# Ethernet.net
KiCad netlist of a schematic drawn in Altium Designer
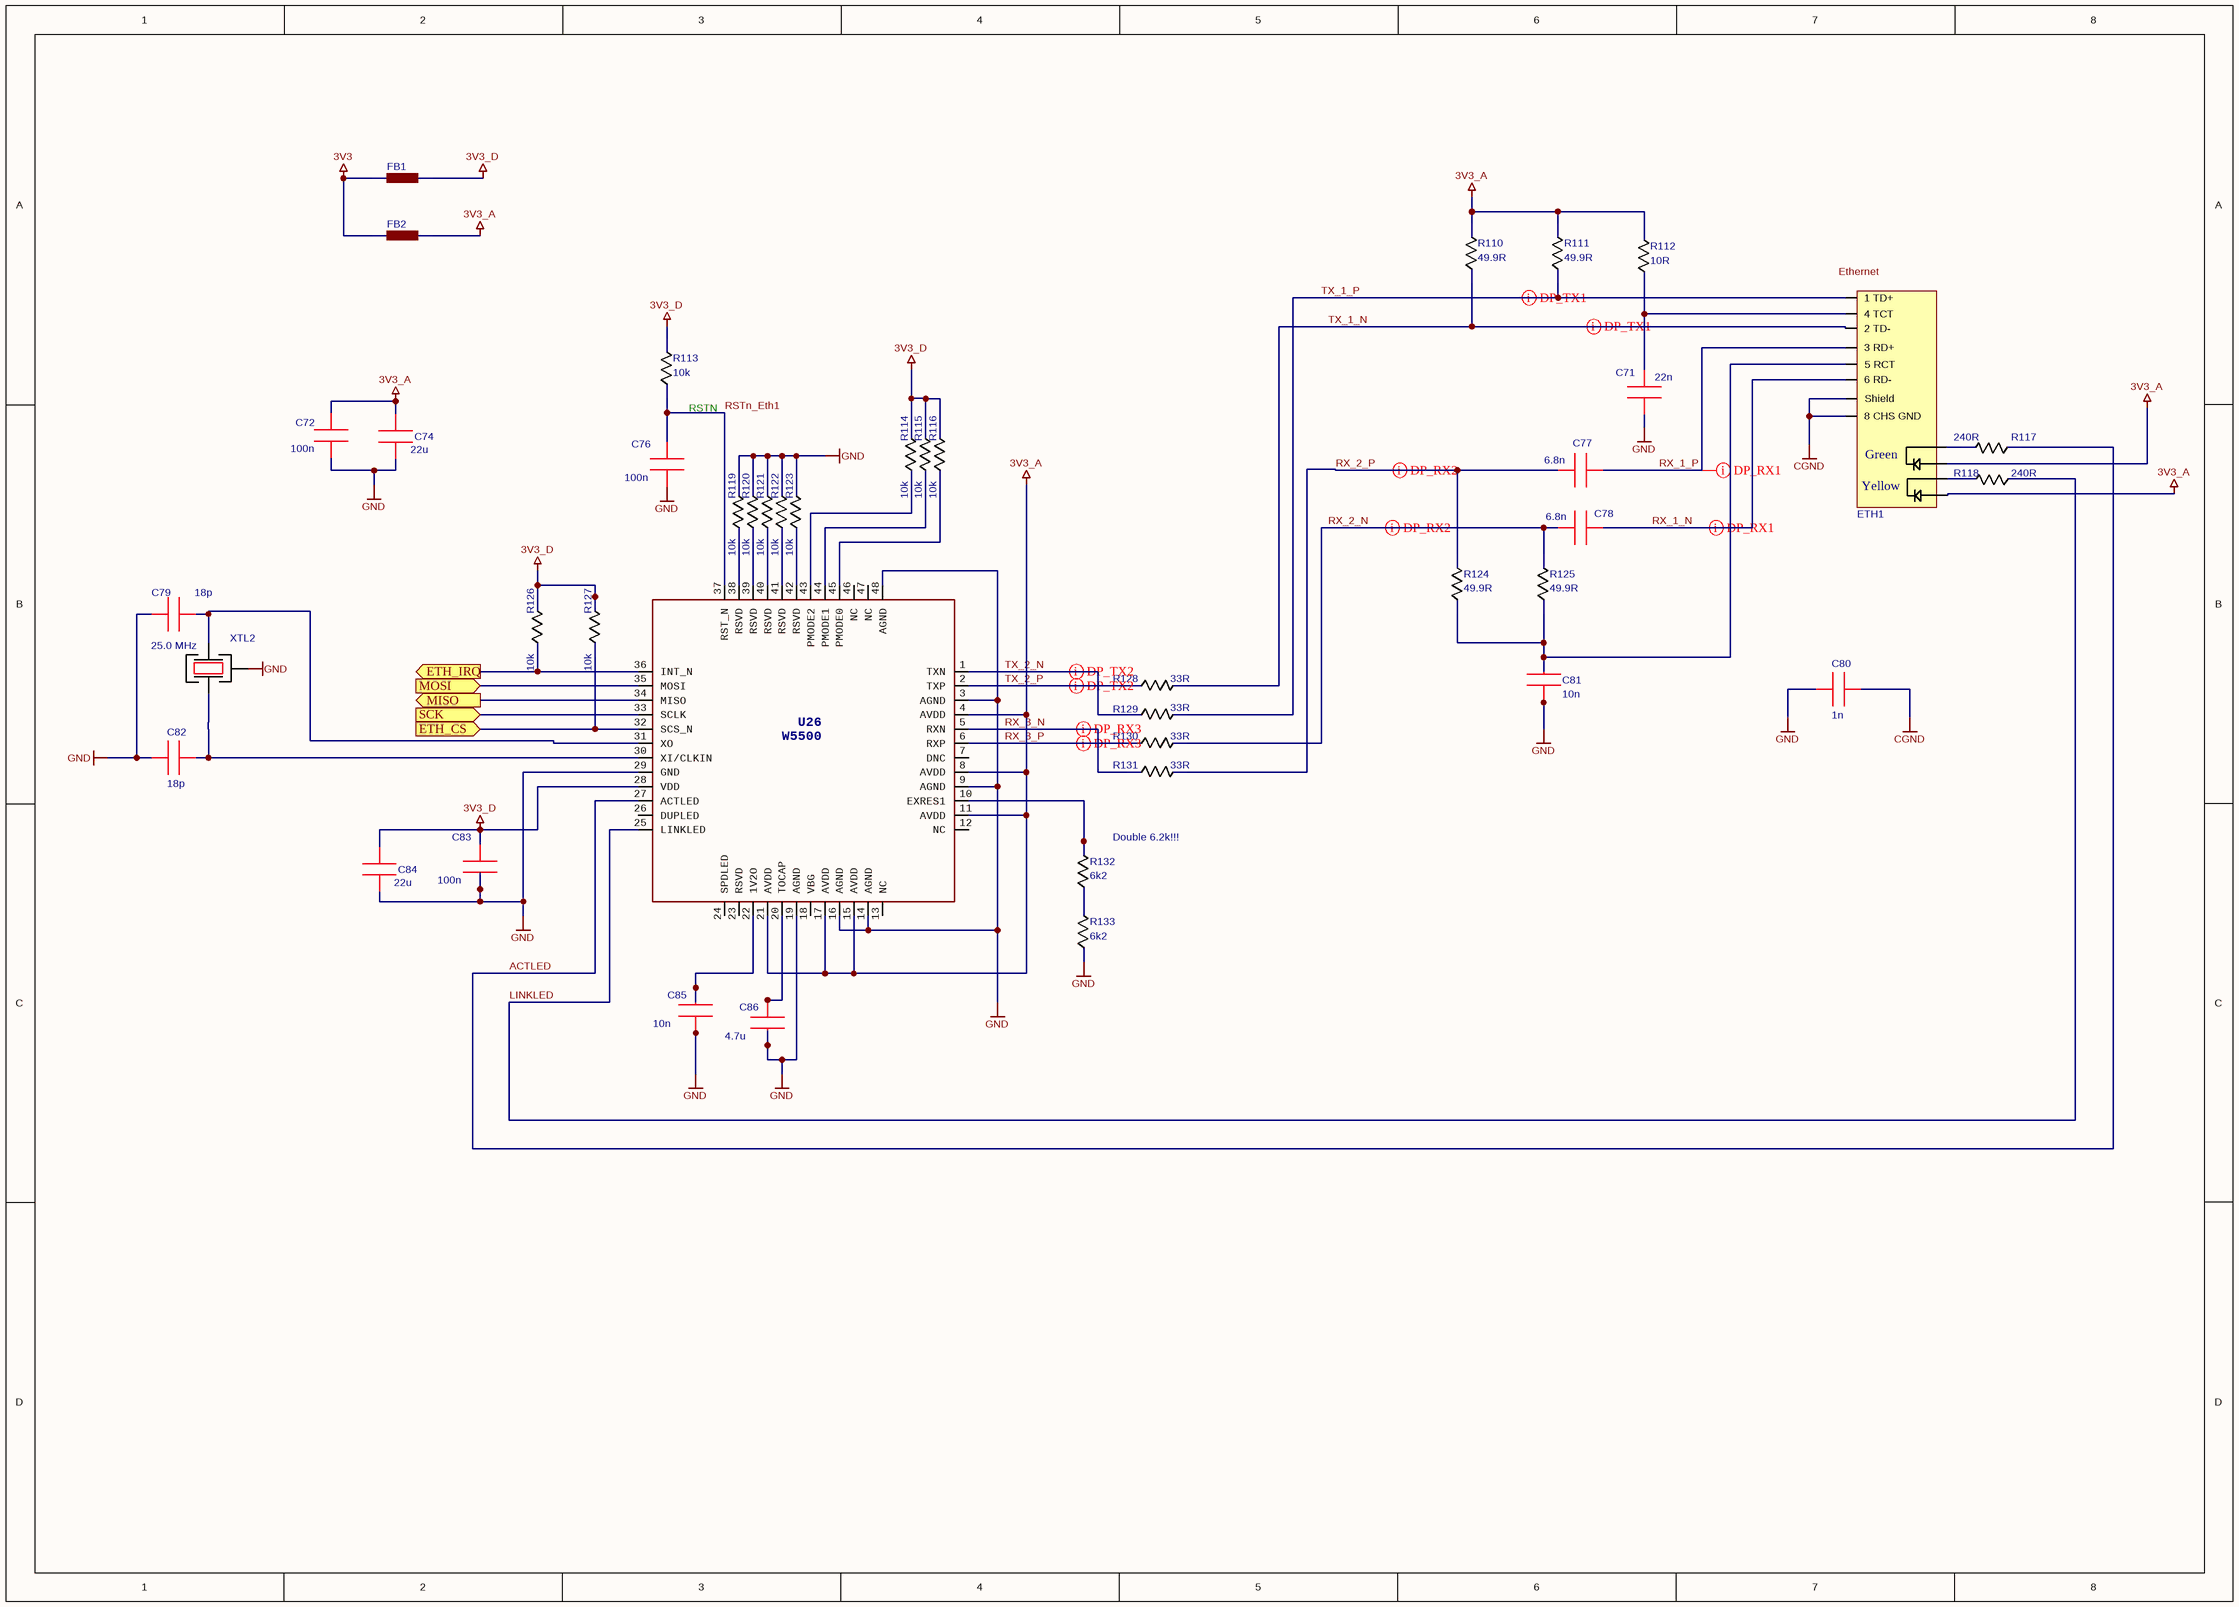
[diagram p0: Ethernet.SchDoc]

(export (version "E")
  (design (tool "Eeschema 10.0.6"))
  (components
    (comp (ref "C71")
      (value "22n")
      (footprint "0603")
      (description "GRM188R71H223KA01D")
      (libsource (lib "kontr") (part "0603 CAP"))
    )
    (comp (ref "C72")
      (value "100n")
      (footprint "0603")
      (description "CC0603KRX7R9BB104")
      (libsource (lib "kontr") (part "0603 CAP"))
    )
    (comp (ref "C74")
      (value "22u")
      (footprint "1206")
      (description "CC1206KKX5R8BB226")
      (libsource (lib "") (part "0805 Cap_1"))
    )
    (comp (ref "C76")
      (value "100n")
      (footprint "0603")
      (description "CC0603KRX7R9BB104")
      (libsource (lib "kontr") (part "0603 CAP"))
    )
    (comp (ref "C77")
      (value "6.8n")
      (footprint "0603")
      (description "CC0603KRX7R9BB682")
      (libsource (lib "kontr") (part "0603 CAP"))
    )
    (comp (ref "C78")
      (value "6.8n")
      (footprint "0603")
      (description "CC0603KRX7R9BB682")
      (libsource (lib "kontr") (part "0603 CAP"))
    )
    (comp (ref "C79")
      (value "18p")
      (footprint "0603")
      (description "CC0603JRNPO9BN180")
      (libsource (lib "kontr") (part "0603 CAP"))
    )
    (comp (ref "C80")
      (value "1n")
      (footprint "1206")
      (description "CC1206KKX7RDBB102")
      (libsource (lib "kontr") (part "0603 CAP"))
    )
    (comp (ref "C81")
      (value "10n")
      (footprint "0603")
      (description "CC0603JRX7R9BB103")
      (libsource (lib "kontr") (part "0603 CAP"))
    )
    (comp (ref "C82")
      (value "18p")
      (footprint "0603")
      (description "CC0603JRNPO9BN180")
      (libsource (lib "kontr") (part "0603 CAP"))
    )
    (comp (ref "C83")
      (value "100n")
      (footprint "0603")
      (description "CC0603KRX7R9BB104")
      (libsource (lib "kontr") (part "0603 CAP"))
    )
    (comp (ref "C84")
      (value "22u")
      (footprint "1206")
      (description "CC1206KKX5R8BB226")
      (libsource (lib "kontr") (part "0805 Cap"))
    )
    (comp (ref "C85")
      (value "10n")
      (footprint "0603")
      (description "CC0603JRX7R9BB103")
      (libsource (lib "kontr") (part "0603 CAP"))
    )
    (comp (ref "C86")
      (value "4.7u")
      (footprint "0603")
      (description "GRM188R61A475KE15D")
      (libsource (lib "kontr") (part "0603 CAP"))
    )
    (comp (ref "ETH1")
      (value "Ethernet RJ-45 Port")
      (footprint "J011D21BNL")
      (description "J0011D21BNL")
      (libsource (lib "kontr") (part "J0011D21BNL"))
    )
    (comp (ref "FB1")
      (value "Ferrite Bead")
      (footprint "0805")
      (description "BLM21PG220SN1D")
      (libsource (lib "kontr") (part "BLM21PG220SN1D"))
    )
    (comp (ref "FB2")
      (value "Ferrite Bead")
      (footprint "0805")
      (description "BLM21PG220SN1D")
      (libsource (lib "kontr") (part "BLM21PG220SN1D"))
    )
    (comp (ref "R110")
      (value "49.9R")
      (footprint "0603")
      (description "RC0603FR-0749R9")
      (libsource (lib "kontr") (part "0603 RES"))
    )
    (comp (ref "R111")
      (value "49.9R")
      (footprint "0603")
      (description "RC0603FR-0749R9")
      (libsource (lib "kontr") (part "0603 RES"))
    )
    (comp (ref "R112")
      (value "10R")
      (footprint "0603")
      (description "RC0603FR-0710RL")
      (libsource (lib "kontr") (part "0603 RES"))
    )
    (comp (ref "R113")
      (value "10k")
      (footprint "0603")
      (description "RC0603FR-0710KL")
      (libsource (lib "kontr") (part "0603 RES"))
    )
    (comp (ref "R114")
      (value "10k")
      (footprint "0603")
      (description "RC0603FR-0710KL")
      (libsource (lib "kontr") (part "0603 RES"))
    )
    (comp (ref "R115")
      (value "10k")
      (footprint "0603")
      (description "RC0603FR-0710KL")
      (libsource (lib "kontr") (part "0603 RES"))
    )
    (comp (ref "R116")
      (value "10k")
      (footprint "0603")
      (description "RC0603FR-0710KL")
      (libsource (lib "kontr") (part "0603 RES"))
    )
    (comp (ref "R117")
      (value "240R")
      (footprint "0603")
      (description "RC0603FR-07240RL")
      (libsource (lib "kontr") (part "0603 RES"))
    )
    (comp (ref "R118")
      (value "240R")
      (footprint "0603")
      (description "RC0603FR-07240RL")
      (libsource (lib "kontr") (part "0603 RES"))
    )
    (comp (ref "R119")
      (value "10k")
      (footprint "0603")
      (description "RC0603FR-0710KL")
      (libsource (lib "kontr") (part "0603 RES"))
    )
    (comp (ref "R120")
      (value "10k")
      (footprint "0603")
      (description "RC0603FR-0710KL")
      (libsource (lib "kontr") (part "0603 RES"))
    )
    (comp (ref "R121")
      (value "10k")
      (footprint "0603")
      (description "RC0603FR-0710KL")
      (libsource (lib "kontr") (part "0603 RES"))
    )
    (comp (ref "R122")
      (value "10k")
      (footprint "0603")
      (description "RC0603FR-0710KL")
      (libsource (lib "kontr") (part "0603 RES"))
    )
    (comp (ref "R123")
      (value "10k")
      (footprint "0603")
      (description "RC0603FR-0710KL")
      (libsource (lib "kontr") (part "0603 RES"))
    )
    (comp (ref "R124")
      (value "49.9R")
      (footprint "0603")
      (description "RC0603FR-0749R9")
      (libsource (lib "kontr") (part "0603 RES"))
    )
    (comp (ref "R125")
      (value "49.9R")
      (footprint "0603")
      (description "RC0603FR-0749R9")
      (libsource (lib "kontr") (part "0603 RES"))
    )
    (comp (ref "R126")
      (value "10k")
      (footprint "0603")
      (description "RC0603FR-0710KL")
      (libsource (lib "kontr") (part "0603 RES"))
    )
    (comp (ref "R127")
      (value "10k")
      (footprint "0603")
      (description "RC0603FR-0710KL")
      (libsource (lib "kontr") (part "0603 RES"))
    )
    (comp (ref "R128")
      (value "33R")
      (footprint "0603")
      (description "RC0603FR-0733R")
      (libsource (lib "kontr") (part "0603 RES"))
    )
    (comp (ref "R129")
      (value "33R")
      (footprint "0603")
      (description "RC0603FR-0733R")
      (libsource (lib "kontr") (part "0603 RES"))
    )
    (comp (ref "R130")
      (value "33R")
      (footprint "0603")
      (description "RC0603FR-0733R")
      (libsource (lib "kontr") (part "0603 RES"))
    )
    (comp (ref "R131")
      (value "33R")
      (footprint "0603")
      (description "RC0603FR-0733R")
      (libsource (lib "kontr") (part "0603 RES"))
    )
    (comp (ref "R132")
      (value "6k2")
      (footprint "0603")
      (description "RC0603FR-076K2")
      (libsource (lib "kontr") (part "0603 RES"))
    )
    (comp (ref "R133")
      (value "6k2")
      (footprint "0603")
      (description "RC0603FR-076K2")
      (libsource (lib "kontr") (part "0603 RES"))
    )
    (comp (ref "U26") (value "W5500") (footprint "LQFP 48") (libsource (lib "W5500") (part "W5500")))
    (comp (ref "XTL2")
      (value "25.0 MHz")
      (footprint "KX-7 XTAL")
      (description "12.88711")
      (libsource (lib "kontr") (part "KX-7"))
    )
  )
  (nets
    (net (code "1") (name "/ACTLED") (class "Default")
      (node (ref "R117") (pin "1") (pintype "passive"))
      (node (ref "U26") (pin "27") (pinfunction "ACTLED_27") (pintype "passive"))
    )
    (net (code "2") (name "/ETH_CS") (class "Default")
      (node (ref "R127") (pin "1") (pintype "passive"))
      (node (ref "U26") (pin "32") (pinfunction "SCS_N_32") (pintype "passive"))
    )
    (net (code "3") (name "/ETH_IRQ") (class "Default")
      (node (ref "R126") (pin "1") (pintype "passive"))
      (node (ref "U26") (pin "36") (pinfunction "INT_N_36") (pintype "passive"))
    )
    (net (code "4") (name "/LINKLED") (class "Default")
      (node (ref "R118") (pin "1") (pintype "passive"))
      (node (ref "U26") (pin "25") (pinfunction "LINKLED_25") (pintype "passive"))
    )
    (net (code "5") (name "/MISO") (class "Default")
      (node (ref "U26") (pin "34") (pinfunction "MISO_34") (pintype "passive"))
    )
    (net (code "6") (name "/MOSI") (class "Default")
      (node (ref "U26") (pin "35") (pinfunction "MOSI_35") (pintype "passive"))
    )
    (net (code "7") (name "/RSTn_Eth1") (class "Default")
      (node (ref "C76") (pin "1") (pinfunction "1_1") (pintype "passive"))
      (node (ref "R113") (pin "1") (pintype "passive"))
      (node (ref "U26") (pin "37") (pinfunction "RST_N_37") (pintype "passive"))
    )
    (net (code "8") (name "/RX_1_N") (class "Default")
      (node (ref "C78") (pin "2") (pinfunction "2_2") (pintype "passive"))
      (node (ref "ETH1") (pin "6") (pinfunction "6_RD-_6") (pintype "passive"))
    )
    (net (code "9") (name "/RX_1_P") (class "Default")
      (node (ref "C77") (pin "2") (pinfunction "2_2") (pintype "passive"))
      (node (ref "ETH1") (pin "3") (pinfunction "3_RD+_3") (pintype "passive"))
    )
    (net (code "10") (name "/RX_2_N") (class "Default")
      (node (ref "C78") (pin "1") (pinfunction "1_1") (pintype "passive"))
      (node (ref "R125") (pin "2") (pintype "passive"))
      (node (ref "R130") (pin "2") (pintype "passive"))
    )
    (net (code "11") (name "/RX_2_P") (class "Default")
      (node (ref "C77") (pin "1") (pinfunction "1_1") (pintype "passive"))
      (node (ref "R124") (pin "2") (pintype "passive"))
      (node (ref "R131") (pin "2") (pintype "passive"))
    )
    (net (code "12") (name "/RX_3_N") (class "Default")
      (node (ref "R131") (pin "1") (pintype "passive"))
      (node (ref "U26") (pin "5") (pinfunction "RXN_5") (pintype "passive"))
    )
    (net (code "13") (name "/RX_3_P") (class "Default")
      (node (ref "R130") (pin "1") (pintype "passive"))
      (node (ref "U26") (pin "6") (pinfunction "RXP_6") (pintype "passive"))
    )
    (net (code "14") (name "/SCK") (class "Default")
      (node (ref "U26") (pin "33") (pinfunction "SCLK_33") (pintype "passive"))
    )
    (net (code "15") (name "/TX_1_N") (class "Default")
      (node (ref "ETH1") (pin "2") (pinfunction "2_TD-_2") (pintype "passive"))
      (node (ref "R110") (pin "1") (pintype "passive"))
      (node (ref "R128") (pin "2") (pintype "passive"))
    )
    (net (code "16") (name "/TX_1_P") (class "Default")
      (node (ref "ETH1") (pin "1") (pinfunction "1_TD+_1") (pintype "passive"))
      (node (ref "R111") (pin "1") (pintype "passive"))
      (node (ref "R129") (pin "2") (pintype "passive"))
    )
    (net (code "17") (name "/TX_2_N") (class "Default")
      (node (ref "R129") (pin "1") (pintype "passive"))
      (node (ref "U26") (pin "1") (pinfunction "TXN_1") (pintype "passive"))
    )
    (net (code "18") (name "/TX_2_P") (class "Default")
      (node (ref "R128") (pin "1") (pintype "passive"))
      (node (ref "U26") (pin "2") (pinfunction "TXP_2") (pintype "passive"))
    )
    (net (code "19") (name "3V3") (class "Default")
      (node (ref "FB1") (pin "1") (pintype "passive"))
      (node (ref "FB2") (pin "1") (pintype "passive"))
    )
    (net (code "20") (name "3V3_A") (class "Default")
      (node (ref "C72") (pin "1") (pinfunction "1_1") (pintype "passive"))
      (node (ref "C74") (pin "2") (pinfunction "2_2") (pintype "passive"))
      (node (ref "ETH1") (pin "12") (pinfunction "LDYE_12") (pintype "passive"))
      (node (ref "ETH1") (pin "9") (pinfunction "LDGr_9") (pintype "passive"))
      (node (ref "FB2") (pin "2") (pintype "passive"))
      (node (ref "R110") (pin "2") (pintype "passive"))
      (node (ref "R111") (pin "2") (pintype "passive"))
      (node (ref "R112") (pin "2") (pintype "passive"))
      (node (ref "U26") (pin "11") (pinfunction "AVDD_11") (pintype "passive"))
      (node (ref "U26") (pin "15") (pinfunction "AVDD_15") (pintype "passive"))
      (node (ref "U26") (pin "17") (pinfunction "AVDD_17") (pintype "passive"))
      (node (ref "U26") (pin "21") (pinfunction "AVDD_21") (pintype "passive"))
      (node (ref "U26") (pin "4") (pinfunction "AVDD_4") (pintype "passive"))
      (node (ref "U26") (pin "8") (pinfunction "AVDD_8") (pintype "passive"))
    )
    (net (code "21") (name "3V3_D") (class "Default")
      (node (ref "C83") (pin "1") (pinfunction "1_1") (pintype "passive"))
      (node (ref "C84") (pin "2") (pinfunction "2_2") (pintype "passive"))
      (node (ref "FB1") (pin "2") (pintype "passive"))
      (node (ref "R113") (pin "2") (pintype "passive"))
      (node (ref "R114") (pin "2") (pintype "passive"))
      (node (ref "R115") (pin "2") (pintype "passive"))
      (node (ref "R116") (pin "2") (pintype "passive"))
      (node (ref "R126") (pin "2") (pintype "passive"))
      (node (ref "R127") (pin "2") (pintype "passive"))
      (node (ref "U26") (pin "28") (pinfunction "VDD_28") (pintype "passive"))
    )
    (net (code "22") (name "CGND") (class "Default")
      (node (ref "C80") (pin "2") (pinfunction "2_2") (pintype "passive"))
      (node (ref "ETH1") (pin "8") (pinfunction "8_CHS_GND_8") (pintype "passive"))
      (node (ref "ETH1") (pin "SHIELD") (pinfunction "Shield_SHIELD") (pintype "passive"))
    )
    (net (code "23") (name "GND") (class "Default")
      (node (ref "C71") (pin "2") (pinfunction "2_2") (pintype "passive"))
      (node (ref "C72") (pin "2") (pinfunction "2_2") (pintype "passive"))
      (node (ref "C74") (pin "1") (pinfunction "1_1") (pintype "passive"))
      (node (ref "C76") (pin "2") (pinfunction "2_2") (pintype "passive"))
      (node (ref "C79") (pin "1") (pinfunction "1_1") (pintype "passive"))
      (node (ref "C80") (pin "1") (pinfunction "1_1") (pintype "passive"))
      (node (ref "C81") (pin "2") (pinfunction "2_2") (pintype "passive"))
      (node (ref "C82") (pin "1") (pinfunction "1_1") (pintype "passive"))
      (node (ref "C83") (pin "2") (pinfunction "2_2") (pintype "passive"))
      (node (ref "C84") (pin "1") (pinfunction "1_1") (pintype "passive"))
      (node (ref "C85") (pin "2") (pinfunction "2_2") (pintype "passive"))
      (node (ref "C86") (pin "2") (pinfunction "2_2") (pintype "passive"))
      (node (ref "R119") (pin "2") (pintype "passive"))
      (node (ref "R120") (pin "2") (pintype "passive"))
      (node (ref "R121") (pin "2") (pintype "passive"))
      (node (ref "R122") (pin "2") (pintype "passive"))
      (node (ref "R123") (pin "2") (pintype "passive"))
      (node (ref "R133") (pin "1") (pintype "passive"))
      (node (ref "U26") (pin "14") (pinfunction "AGND_14") (pintype "passive"))
      (node (ref "U26") (pin "16") (pinfunction "AGND_16") (pintype "passive"))
      (node (ref "U26") (pin "19") (pinfunction "AGND_19") (pintype "passive"))
      (node (ref "U26") (pin "29") (pinfunction "GND_29") (pintype "passive"))
      (node (ref "U26") (pin "3") (pinfunction "AGND_3") (pintype "passive"))
      (node (ref "U26") (pin "48") (pinfunction "AGND_48") (pintype "passive"))
      (node (ref "U26") (pin "9") (pinfunction "AGND_9") (pintype "passive"))
      (node (ref "XTL2") (pin "2") (pinfunction "2_2") (pintype "passive"))
    )
    (net (code "24") (name "Net-(ETH1-4_TCT)") (class "Default")
      (node (ref "C71") (pin "1") (pinfunction "1_1") (pintype "passive"))
      (node (ref "ETH1") (pin "4") (pinfunction "4_TCT_4") (pintype "passive"))
      (node (ref "R112") (pin "1") (pintype "passive"))
    )
    (net (code "25") (name "Net-(ETH1-5_RCT)") (class "Default")
      (node (ref "C81") (pin "1") (pinfunction "1_1") (pintype "passive"))
      (node (ref "ETH1") (pin "5") (pinfunction "5_RCT_5") (pintype "passive"))
      (node (ref "R124") (pin "1") (pintype "passive"))
      (node (ref "R125") (pin "1") (pintype "passive"))
    )
    (net (code "26") (name "Net-(ETH1-LDGr-Pad10)") (class "Default")
      (node (ref "ETH1") (pin "10") (pinfunction "LDGr_10") (pintype "passive"))
      (node (ref "R117") (pin "2") (pintype "passive"))
    )
    (net (code "27") (name "Net-(ETH1-LDYE-Pad11)") (class "Default")
      (node (ref "ETH1") (pin "11") (pinfunction "LDYE_11") (pintype "passive"))
      (node (ref "R118") (pin "2") (pintype "passive"))
    )
    (net (code "28") (name "Net-(R119-Pad1)") (class "Default")
      (node (ref "R119") (pin "1") (pintype "passive"))
      (node (ref "U26") (pin "38") (pinfunction "RSVD_38") (pintype "passive"))
    )
    (net (code "29") (name "Net-(R120-Pad1)") (class "Default")
      (node (ref "R120") (pin "1") (pintype "passive"))
      (node (ref "U26") (pin "39") (pinfunction "RSVD_39") (pintype "passive"))
    )
    (net (code "30") (name "Net-(R121-Pad1)") (class "Default")
      (node (ref "R121") (pin "1") (pintype "passive"))
      (node (ref "U26") (pin "40") (pinfunction "RSVD_40") (pintype "passive"))
    )
    (net (code "31") (name "Net-(R122-Pad1)") (class "Default")
      (node (ref "R122") (pin "1") (pintype "passive"))
      (node (ref "U26") (pin "41") (pinfunction "RSVD_41") (pintype "passive"))
    )
    (net (code "32") (name "Net-(R123-Pad1)") (class "Default")
      (node (ref "R123") (pin "1") (pintype "passive"))
      (node (ref "U26") (pin "42") (pinfunction "RSVD_42") (pintype "passive"))
    )
    (net (code "33") (name "Net-(R132-Pad1)") (class "Default")
      (node (ref "R132") (pin "1") (pintype "passive"))
      (node (ref "R133") (pin "2") (pintype "passive"))
    )
    (net (code "34") (name "Net-(U26-1V2O)") (class "Default")
      (node (ref "C85") (pin "1") (pinfunction "1_1") (pintype "passive"))
      (node (ref "U26") (pin "22") (pinfunction "1V2O_22") (pintype "passive"))
    )
    (net (code "35") (name "Net-(U26-EXRES1)") (class "Default")
      (node (ref "R132") (pin "2") (pintype "passive"))
      (node (ref "U26") (pin "10") (pinfunction "EXRES1_10") (pintype "passive"))
    )
    (net (code "36") (name "Net-(U26-PMODE0)") (class "Default")
      (node (ref "R116") (pin "1") (pintype "passive"))
      (node (ref "U26") (pin "45") (pinfunction "PMODE0_45") (pintype "passive"))
    )
    (net (code "37") (name "Net-(U26-PMODE1)") (class "Default")
      (node (ref "R115") (pin "1") (pintype "passive"))
      (node (ref "U26") (pin "44") (pinfunction "PMODE1_44") (pintype "passive"))
    )
    (net (code "38") (name "Net-(U26-PMODE2)") (class "Default")
      (node (ref "R114") (pin "1") (pintype "passive"))
      (node (ref "U26") (pin "43") (pinfunction "PMODE2_43") (pintype "passive"))
    )
    (net (code "39") (name "Net-(U26-TOCAP)") (class "Default")
      (node (ref "C86") (pin "1") (pinfunction "1_1") (pintype "passive"))
      (node (ref "U26") (pin "20") (pinfunction "TOCAP_20") (pintype "passive"))
    )
    (net (code "40") (name "Net-(U26-XI{slash}CLKIN)") (class "Default")
      (node (ref "C82") (pin "2") (pinfunction "2_2") (pintype "passive"))
      (node (ref "U26") (pin "30") (pinfunction "XI/CLKIN_30") (pintype "passive"))
      (node (ref "XTL2") (pin "1") (pinfunction "5_1") (pintype "passive"))
    )
    (net (code "41") (name "Net-(U26-XO)") (class "Default")
      (node (ref "C79") (pin "2") (pinfunction "2_2") (pintype "passive"))
      (node (ref "U26") (pin "31") (pinfunction "XO_31") (pintype "passive"))
      (node (ref "XTL2") (pin "3") (pinfunction "5_3") (pintype "passive"))
    )
    (net (code "42") (name "unconnected-(U26-DNC-Pad7)") (class "Default")
      (node (ref "U26") (pin "7") (pinfunction "DNC_7") (pintype "passive"))
    )
    (net (code "43") (name "unconnected-(U26-DUPLED-Pad26)") (class "Default")
      (node (ref "U26") (pin "26") (pinfunction "DUPLED_26") (pintype "passive"))
    )
    (net (code "44") (name "unconnected-(U26-NC-Pad12)") (class "Default")
      (node (ref "U26") (pin "12") (pinfunction "NC_12") (pintype "passive"))
    )
    (net (code "45") (name "unconnected-(U26-NC-Pad13)") (class "Default")
      (node (ref "U26") (pin "13") (pinfunction "NC_13") (pintype "passive"))
    )
    (net (code "46") (name "unconnected-(U26-NC-Pad46)") (class "Default")
      (node (ref "U26") (pin "46") (pinfunction "NC_46") (pintype "passive"))
    )
    (net (code "47") (name "unconnected-(U26-NC-Pad47)") (class "Default")
      (node (ref "U26") (pin "47") (pinfunction "NC_47") (pintype "passive"))
    )
    (net (code "48") (name "unconnected-(U26-RSVD-Pad23)") (class "Default")
      (node (ref "U26") (pin "23") (pinfunction "RSVD_23") (pintype "passive"))
    )
    (net (code "49") (name "unconnected-(U26-SPDLED-Pad24)") (class "Default")
      (node (ref "U26") (pin "24") (pinfunction "SPDLED_24") (pintype "passive"))
    )
    (net (code "50") (name "unconnected-(U26-VBG-Pad18)") (class "Default")
      (node (ref "U26") (pin "18") (pinfunction "VBG_18") (pintype "passive"))
    )
  )
)
